# Sheet1.net
KiCad netlist of a schematic drawn in Altium Designer
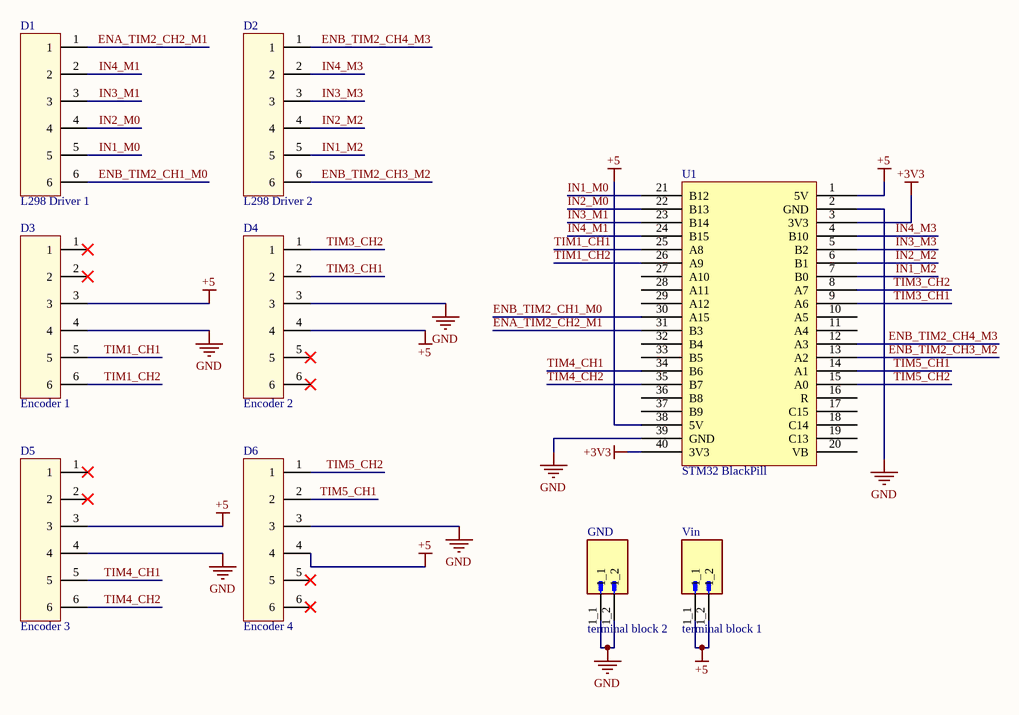
[diagram p0: Sheet1.SchDoc]

(export (version "E")
  (design (tool "Eeschema 10.0.6"))
  (components
    (comp (ref "D1")
      (value "L298 Driver 1")
      (footprint "DATA_PIN_HEADER_6_2.54m")
      (libsource (lib "My Library") (part "DATA_PIN_HEADER_6_2.54m"))
    )
    (comp (ref "D2")
      (value "L298 Driver 2")
      (footprint "DATA_PIN_HEADER_6_2.54m")
      (libsource (lib "My Library") (part "DATA_PIN_HEADER_6_2.54m"))
    )
    (comp (ref "D3")
      (value "Encoder 1")
      (footprint "DATA_PIN_HEADER_6_2.54m")
      (libsource (lib "My Library") (part "DATA_PIN_HEADER_6_2.54m"))
    )
    (comp (ref "D4")
      (value "Encoder 2")
      (footprint "DATA_PIN_HEADER_6_2.54m")
      (libsource (lib "My Library") (part "DATA_PIN_HEADER_6_2.54m"))
    )
    (comp (ref "D5")
      (value "Encoder 3")
      (footprint "DATA_PIN_HEADER_6_2.54m")
      (libsource (lib "My Library") (part "DATA_PIN_HEADER_6_2.54m"))
    )
    (comp (ref "D6")
      (value "Encoder 4")
      (footprint "DATA_PIN_HEADER_6_2.54m")
      (libsource (lib "My Library") (part "DATA_PIN_HEADER_6_2.54m"))
    )
    (comp (ref "GND")
      (value "terminal block 2")
      (footprint "KEYSTONE_1287")
      (description "Male .250 Quick Fit Terminal")
      (fields (field (name "MF") "Keystone Electronics Corp.") (field (name "MP") "1287"))
      (libsource (lib "1287") (part "1287"))
    )
    (comp (ref "U1")
      (value "STM32 BlackPill")
      (footprint "STM 32 Black Pill")
      (description "STM32F401CC")
      (libsource (lib "My Library") (part "STM32 BlackPill"))
    )
    (comp (ref "Vin")
      (value "terminal block 1")
      (footprint "KEYSTONE_1287")
      (description "Male .250 Quick Fit Terminal")
      (fields (field (name "MF") "Keystone Electronics Corp.") (field (name "MP") "1287"))
      (libsource (lib "1287") (part "1287"))
    )
  )
  (nets
    (net (code "1") (name "+3V3") (class "Default")
      (node (ref "U1") (pin "3") (pinfunction "3V3_3") (pintype "passive"))
      (node (ref "U1") (pin "40") (pinfunction "3V3_40") (pintype "passive"))
    )
    (net (code "2") (name "+5") (class "Default")
      (node (ref "D3") (pin "3") (pinfunction "3_3") (pintype "passive"))
      (node (ref "D4") (pin "4") (pinfunction "4_4") (pintype "passive"))
      (node (ref "D5") (pin "3") (pinfunction "3_3") (pintype "passive"))
      (node (ref "D6") (pin "4") (pinfunction "4_4") (pintype "passive"))
      (node (ref "U1") (pin "1") (pinfunction "5V_1") (pintype "passive"))
      (node (ref "U1") (pin "38") (pinfunction "5V_38") (pintype "passive"))
      (node (ref "Vin") (pin "1_1") (pinfunction "1_1_1_1") (pintype "passive"))
      (node (ref "Vin") (pin "1_2") (pinfunction "1_2_1_2") (pintype "passive"))
    )
    (net (code "3") (name "/ENA_TIM2_CH2_M1") (class "Default")
      (node (ref "D1") (pin "1") (pinfunction "1_1") (pintype "passive"))
      (node (ref "U1") (pin "31") (pinfunction "B3_31") (pintype "passive"))
    )
    (net (code "4") (name "/ENB_TIM2_CH1_M0") (class "Default")
      (node (ref "D1") (pin "6") (pinfunction "6_6") (pintype "passive"))
      (node (ref "U1") (pin "30") (pinfunction "A15_30") (pintype "passive"))
    )
    (net (code "5") (name "/ENB_TIM2_CH3_M2") (class "Default")
      (node (ref "D2") (pin "6") (pinfunction "6_6") (pintype "passive"))
      (node (ref "U1") (pin "13") (pinfunction "A2_13") (pintype "passive"))
    )
    (net (code "6") (name "/ENB_TIM2_CH4_M3") (class "Default")
      (node (ref "D2") (pin "1") (pinfunction "1_1") (pintype "passive"))
      (node (ref "U1") (pin "12") (pinfunction "A3_12") (pintype "passive"))
    )
    (net (code "7") (name "/IN1_M0") (class "Default")
      (node (ref "D1") (pin "5") (pinfunction "5_5") (pintype "passive"))
      (node (ref "U1") (pin "21") (pinfunction "B12_21") (pintype "passive"))
    )
    (net (code "8") (name "/IN1_M2") (class "Default")
      (node (ref "D2") (pin "5") (pinfunction "5_5") (pintype "passive"))
      (node (ref "U1") (pin "7") (pinfunction "B0_7") (pintype "passive"))
    )
    (net (code "9") (name "/IN2_M0") (class "Default")
      (node (ref "D1") (pin "4") (pinfunction "4_4") (pintype "passive"))
      (node (ref "U1") (pin "22") (pinfunction "B13_22") (pintype "passive"))
    )
    (net (code "10") (name "/IN2_M2") (class "Default")
      (node (ref "D2") (pin "4") (pinfunction "4_4") (pintype "passive"))
      (node (ref "U1") (pin "6") (pinfunction "B1_6") (pintype "passive"))
    )
    (net (code "11") (name "/IN3_M1") (class "Default")
      (node (ref "D1") (pin "3") (pinfunction "3_3") (pintype "passive"))
      (node (ref "U1") (pin "23") (pinfunction "B14_23") (pintype "passive"))
    )
    (net (code "12") (name "/IN3_M3") (class "Default")
      (node (ref "D2") (pin "3") (pinfunction "3_3") (pintype "passive"))
      (node (ref "U1") (pin "5") (pinfunction "B2_5") (pintype "passive"))
    )
    (net (code "13") (name "/IN4_M1") (class "Default")
      (node (ref "D1") (pin "2") (pinfunction "2_2") (pintype "passive"))
      (node (ref "U1") (pin "24") (pinfunction "B15_24") (pintype "passive"))
    )
    (net (code "14") (name "/IN4_M3") (class "Default")
      (node (ref "D2") (pin "2") (pinfunction "2_2") (pintype "passive"))
      (node (ref "U1") (pin "4") (pinfunction "B10_4") (pintype "passive"))
    )
    (net (code "15") (name "/TIM1_CH1") (class "Default")
      (node (ref "D3") (pin "5") (pinfunction "5_5") (pintype "passive"))
      (node (ref "U1") (pin "25") (pinfunction "A8_25") (pintype "passive"))
    )
    (net (code "16") (name "/TIM1_CH2") (class "Default")
      (node (ref "D3") (pin "6") (pinfunction "6_6") (pintype "passive"))
      (node (ref "U1") (pin "26") (pinfunction "A9_26") (pintype "passive"))
    )
    (net (code "17") (name "/TIM3_CH1") (class "Default")
      (node (ref "D4") (pin "2") (pinfunction "2_2") (pintype "passive"))
      (node (ref "U1") (pin "9") (pinfunction "A6_9") (pintype "passive"))
    )
    (net (code "18") (name "/TIM3_CH2") (class "Default")
      (node (ref "D4") (pin "1") (pinfunction "1_1") (pintype "passive"))
      (node (ref "U1") (pin "8") (pinfunction "A7_8") (pintype "passive"))
    )
    (net (code "19") (name "/TIM4_CH1") (class "Default")
      (node (ref "D5") (pin "5") (pinfunction "5_5") (pintype "passive"))
      (node (ref "U1") (pin "34") (pinfunction "B6_34") (pintype "passive"))
    )
    (net (code "20") (name "/TIM4_CH2") (class "Default")
      (node (ref "D5") (pin "6") (pinfunction "6_6") (pintype "passive"))
      (node (ref "U1") (pin "35") (pinfunction "B7_35") (pintype "passive"))
    )
    (net (code "21") (name "/TIM5_CH1") (class "Default")
      (node (ref "D6") (pin "2") (pinfunction "2_2") (pintype "passive"))
      (node (ref "U1") (pin "14") (pinfunction "A1_14") (pintype "passive"))
    )
    (net (code "22") (name "/TIM5_CH2") (class "Default")
      (node (ref "D6") (pin "1") (pinfunction "1_1") (pintype "passive"))
      (node (ref "U1") (pin "15") (pinfunction "A0_15") (pintype "passive"))
    )
    (net (code "23") (name "GND") (class "Default")
      (node (ref "D3") (pin "4") (pinfunction "4_4") (pintype "passive"))
      (node (ref "D4") (pin "3") (pinfunction "3_3") (pintype "passive"))
      (node (ref "D5") (pin "4") (pinfunction "4_4") (pintype "passive"))
      (node (ref "D6") (pin "3") (pinfunction "3_3") (pintype "passive"))
      (node (ref "GND") (pin "1_1") (pinfunction "1_1_1_1") (pintype "passive"))
      (node (ref "GND") (pin "1_2") (pinfunction "1_2_1_2") (pintype "passive"))
      (node (ref "U1") (pin "2") (pinfunction "GND_2") (pintype "passive"))
      (node (ref "U1") (pin "39") (pinfunction "GND_39") (pintype "passive"))
    )
    (net (code "24") (name "unconnected-(D3-Pad1)") (class "Default")
      (node (ref "D3") (pin "1") (pinfunction "1_1") (pintype "passive+no_connect"))
    )
    (net (code "25") (name "unconnected-(D3-Pad2)") (class "Default")
      (node (ref "D3") (pin "2") (pinfunction "2_2") (pintype "passive+no_connect"))
    )
    (net (code "26") (name "unconnected-(D4-Pad5)") (class "Default")
      (node (ref "D4") (pin "5") (pinfunction "5_5") (pintype "passive+no_connect"))
    )
    (net (code "27") (name "unconnected-(D4-Pad6)") (class "Default")
      (node (ref "D4") (pin "6") (pinfunction "6_6") (pintype "passive+no_connect"))
    )
    (net (code "28") (name "unconnected-(D5-Pad1)") (class "Default")
      (node (ref "D5") (pin "1") (pinfunction "1_1") (pintype "passive+no_connect"))
    )
    (net (code "29") (name "unconnected-(D5-Pad2)") (class "Default")
      (node (ref "D5") (pin "2") (pinfunction "2_2") (pintype "passive+no_connect"))
    )
    (net (code "30") (name "unconnected-(D6-Pad5)") (class "Default")
      (node (ref "D6") (pin "5") (pinfunction "5_5") (pintype "passive+no_connect"))
    )
    (net (code "31") (name "unconnected-(D6-Pad6)") (class "Default")
      (node (ref "D6") (pin "6") (pinfunction "6_6") (pintype "passive+no_connect"))
    )
    (net (code "32") (name "unconnected-(U1-A4-Pad11)") (class "Default")
      (node (ref "U1") (pin "11") (pinfunction "A4_11") (pintype "passive"))
    )
    (net (code "33") (name "unconnected-(U1-A5-Pad10)") (class "Default")
      (node (ref "U1") (pin "10") (pinfunction "A5_10") (pintype "passive"))
    )
    (net (code "34") (name "unconnected-(U1-A10-Pad27)") (class "Default")
      (node (ref "U1") (pin "27") (pinfunction "A10_27") (pintype "passive"))
    )
    (net (code "35") (name "unconnected-(U1-A11-Pad28)") (class "Default")
      (node (ref "U1") (pin "28") (pinfunction "A11_28") (pintype "passive"))
    )
    (net (code "36") (name "unconnected-(U1-A12-Pad29)") (class "Default")
      (node (ref "U1") (pin "29") (pinfunction "A12_29") (pintype "passive"))
    )
    (net (code "37") (name "unconnected-(U1-B4-Pad32)") (class "Default")
      (node (ref "U1") (pin "32") (pinfunction "B4_32") (pintype "passive"))
    )
    (net (code "38") (name "unconnected-(U1-B5-Pad33)") (class "Default")
      (node (ref "U1") (pin "33") (pinfunction "B5_33") (pintype "passive"))
    )
    (net (code "39") (name "unconnected-(U1-B8-Pad36)") (class "Default")
      (node (ref "U1") (pin "36") (pinfunction "B8_36") (pintype "passive"))
    )
    (net (code "40") (name "unconnected-(U1-B9-Pad37)") (class "Default")
      (node (ref "U1") (pin "37") (pinfunction "B9_37") (pintype "passive"))
    )
    (net (code "41") (name "unconnected-(U1-C13-Pad19)") (class "Default")
      (node (ref "U1") (pin "19") (pinfunction "C13_19") (pintype "passive"))
    )
    (net (code "42") (name "unconnected-(U1-C14-Pad18)") (class "Default")
      (node (ref "U1") (pin "18") (pinfunction "C14_18") (pintype "passive"))
    )
    (net (code "43") (name "unconnected-(U1-C15-Pad17)") (class "Default")
      (node (ref "U1") (pin "17") (pinfunction "C15_17") (pintype "passive"))
    )
    (net (code "44") (name "unconnected-(U1-R-Pad16)") (class "Default")
      (node (ref "U1") (pin "16") (pinfunction "R_16") (pintype "passive"))
    )
    (net (code "45") (name "unconnected-(U1-VB-Pad20)") (class "Default")
      (node (ref "U1") (pin "20") (pinfunction "VB_20") (pintype "passive"))
    )
  )
)
